# Experiment_4_0_0_0.net
KiCad netlist of a schematic drawn in Altium Designer
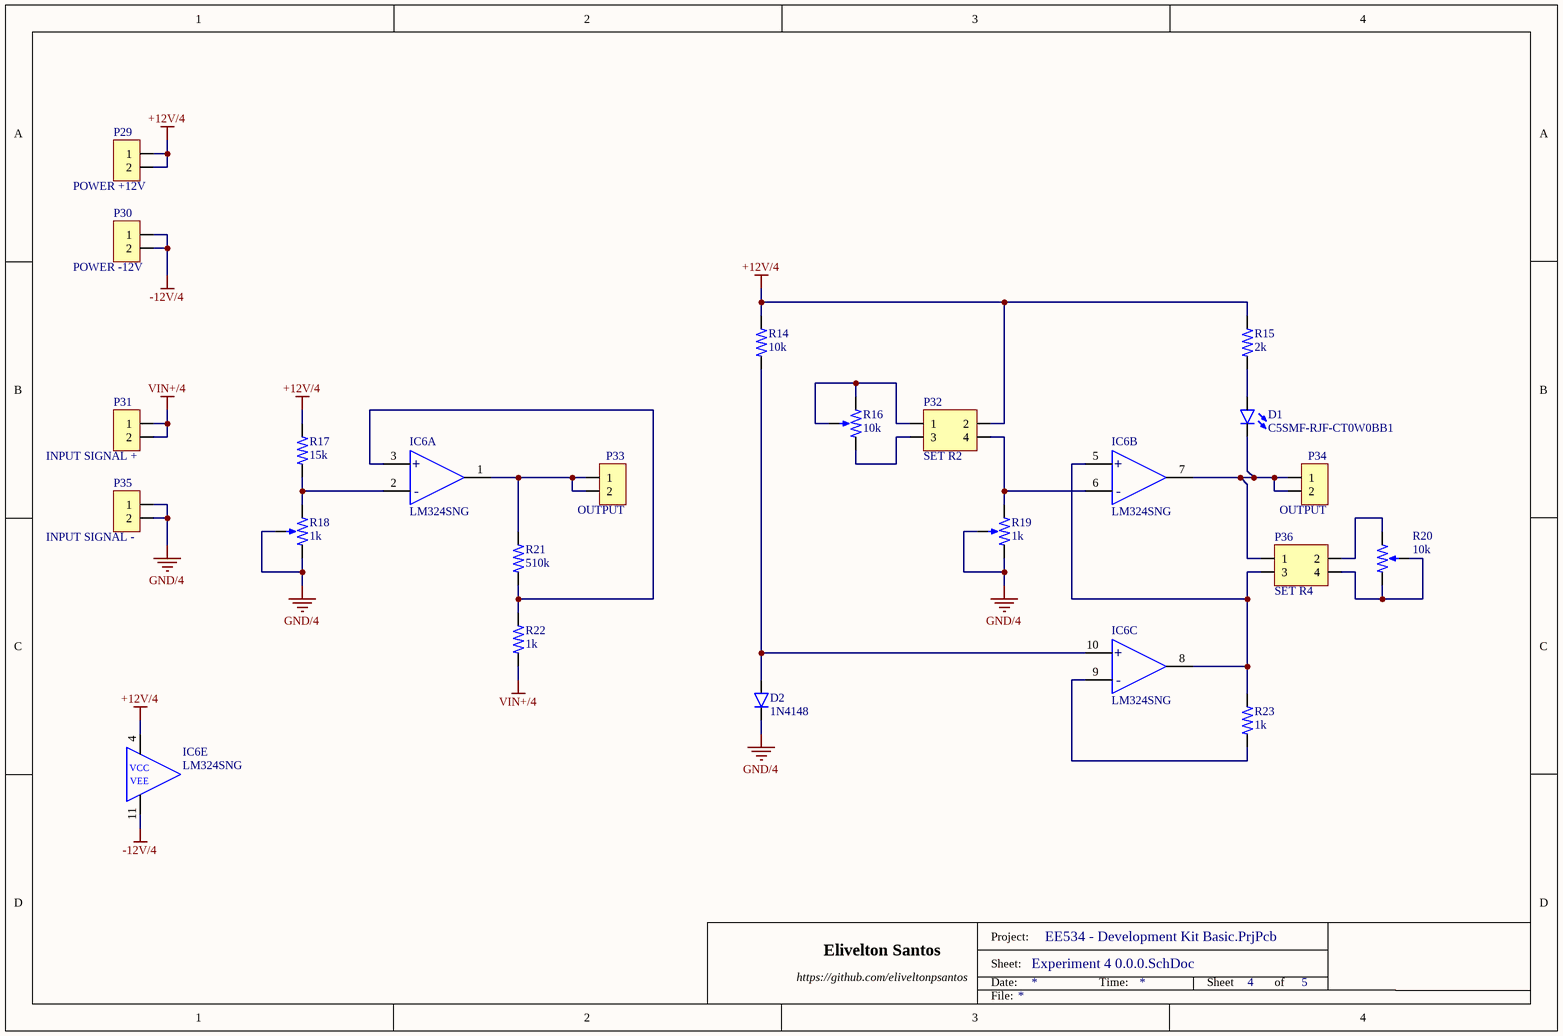
[diagram p0: Experiment 4 0.0.0.SchDoc]

(export (version "E")
  (design (tool "Eeschema 10.0.6"))
  (components
    (comp (ref "D1")
      (value "C5SMF-RJF-CT0W0BB1")
      (footprint "LED-5MM")
      (description "LED RED CLEAR 5MM OVAL T/H")
      (fields (field (name "MANUFACTURER") "Cree Inc."))
      (libsource (lib "Optoelectronics") (part "C5SMF-RJF-CT0W0BB1"))
    )
    (comp (ref "D2")
      (value "1N4148")
      (footprint "DO35-10")
      (description "DIODE GEN PURP 100V 200MA DO35")
      (fields (field (name "MANUFACTURER") "Fairchild Semiconductor"))
      (libsource (lib "Diodes") (part "1N4148"))
    )
    (comp (ref "IC6")
      (value "LM324SNG")
      (footprint "DIP-14")
      (description "IC OP AMP 4CH 14DIP")
      (fields (field (name "MANUFACTURER") "ON Semiconductor"))
      (libsource (lib "ICs") (part "LM324SNG"))
    )
    (comp (ref "P29")
      (value "POWER +12V")
      (footprint "PINHD-1X02 ONCE")
      (description "CONN HEADER 2POS .100\" STR TIN")
      (fields
        (field (name "MANUFACTURER") "Molex, LLC")
        (field (name "MANUFACTURER PART NUMBER") "0901200122")
      )
      (libsource (lib "Connectors") (part "PIN HEADER 1X02 ONCE"))
    )
    (comp (ref "P30")
      (value "POWER -12V")
      (footprint "PINHD-1X02 ONCE")
      (description "CONN HEADER 2POS .100\" STR TIN")
      (fields
        (field (name "MANUFACTURER") "Molex, LLC")
        (field (name "MANUFACTURER PART NUMBER") "0901200122")
      )
      (libsource (lib "Connectors") (part "PIN HEADER 1X02 ONCE"))
    )
    (comp (ref "P31")
      (value "INPUT SIGNAL +")
      (footprint "PINHD-1X02 ONCE")
      (description "CONN HEADER 2POS .100\" STR TIN")
      (fields
        (field (name "MANUFACTURER") "Molex, LLC")
        (field (name "MANUFACTURER PART NUMBER") "0901200122")
      )
      (libsource (lib "Connectors") (part "PIN HEADER 1X02 ONCE"))
    )
    (comp (ref "P32")
      (value "SET R2")
      (footprint "PINHD-2X02")
      (description "CONN HEADER 4POS .100\" STR TIN")
      (fields
        (field (name "MANUFACTURER") "Molex, LLC")
        (field (name "MANUFACTURER PART NUMBER") "0901310122")
      )
      (libsource (lib "Connectors") (part "PIN HEADER 2X02"))
    )
    (comp (ref "P33")
      (value "OUTPUT")
      (footprint "PINHD-1X02 ONCE")
      (description "CONN HEADER 2POS .100\" STR TIN")
      (fields
        (field (name "MANUFACTURER") "Molex, LLC")
        (field (name "MANUFACTURER PART NUMBER") "0901200122")
      )
      (libsource (lib "") (part "PIN HEADER 1X02 ONCE_1"))
    )
    (comp (ref "P34")
      (value "OUTPUT")
      (footprint "PINHD-1X02 ONCE")
      (description "CONN HEADER 2POS .100\" STR TIN")
      (fields
        (field (name "MANUFACTURER") "Molex, LLC")
        (field (name "MANUFACTURER PART NUMBER") "0901200122")
      )
      (libsource (lib "") (part "PIN HEADER 1X02 ONCE_1"))
    )
    (comp (ref "P35")
      (value "INPUT SIGNAL -")
      (footprint "PINHD-1X02 ONCE")
      (description "CONN HEADER 2POS .100\" STR TIN")
      (fields
        (field (name "MANUFACTURER") "Molex, LLC")
        (field (name "MANUFACTURER PART NUMBER") "0901200122")
      )
      (libsource (lib "Connectors") (part "PIN HEADER 1X02 ONCE"))
    )
    (comp (ref "P36")
      (value "SET R4")
      (footprint "PINHD-2X02")
      (description "CONN HEADER 4POS .100\" STR TIN")
      (fields
        (field (name "MANUFACTURER") "Molex, LLC")
        (field (name "MANUFACTURER PART NUMBER") "0901310122")
      )
      (libsource (lib "Connectors") (part "PIN HEADER 2X02"))
    )
    (comp (ref "R14")
      (value "10k")
      (footprint "R Axial 0.25")
      (description "RES 10K OHM 1/4W 5% AXIAL")
      (fields
        (field (name "MANUFACTURER") "Yageo")
        (field (name "MANUFACTURER PART NUMBER") "CFR-25JB-52-10K")
      )
      (libsource (lib "Resistors") (part "CFR-25JB-52-10K"))
    )
    (comp (ref "R15")
      (value "2k")
      (footprint "R Axial 0.25")
      (description "RES 2K OHM 1/4W 5% AXIAL")
      (fields
        (field (name "MANUFACTURER") "Yageo")
        (field (name "MANUFACTURER PART NUMBER") "CFR-25JB-52-2K")
      )
      (libsource (lib "Resistors") (part "CFR-25JB-52-2K"))
    )
    (comp (ref "R16")
      (value "10k")
      (footprint "PV36W")
      (description "TRIMMER 10K OHM 0.5W TH")
      (fields
        (field (name "MANUFACTURER") "Bourns Inc.")
        (field (name "MANUFACTURER PART NUMBER") "PV36W103C01B00")
      )
      (libsource (lib "Resistors") (part "PV36W103C01B00"))
    )
    (comp (ref "R17")
      (value "15k")
      (footprint "R Axial 0.25")
      (description "RES 15K OHM 1/4W 5% AXIAL")
      (fields
        (field (name "MANUFACTURER") "Yageo")
        (field (name "MANUFACTURER PART NUMBER") "CFR-25JB-52-15K")
      )
      (libsource (lib "Resistors") (part "CFR-25JB-52-15K"))
    )
    (comp (ref "R18")
      (value "1k")
      (footprint "PV36W")
      (description "TRIMMER 1K OHM 0.5W TH")
      (fields
        (field (name "MANUFACTURER") "Bourns Inc.")
        (field (name "MANUFACTURER PART NUMBER") "PV36W102C01B00")
      )
      (libsource (lib "Resistors") (part "PV36W102C01B00"))
    )
    (comp (ref "R19")
      (value "1k")
      (footprint "PV36W")
      (description "TRIMMER 1K OHM 0.5W TH")
      (fields
        (field (name "MANUFACTURER") "Bourns Inc.")
        (field (name "MANUFACTURER PART NUMBER") "PV36W102C01B00")
      )
      (libsource (lib "Resistors") (part "PV36W102C01B00"))
    )
    (comp (ref "R20")
      (value "10k")
      (footprint "PV36W")
      (description "TRIMMER 10K OHM 0.5W TH")
      (fields
        (field (name "MANUFACTURER") "Bourns Inc.")
        (field (name "MANUFACTURER PART NUMBER") "PV36W103C01B00")
      )
      (libsource (lib "Resistors") (part "PV36W103C01B00"))
    )
    (comp (ref "R21")
      (value "510k")
      (footprint "R Axial 0.25")
      (description "RES 510K OHM 1/4W 5% AXIAL")
      (fields
        (field (name "MANUFACTURER") "Yageo")
        (field (name "MANUFACTURER PART NUMBER") "CFR-25JB-52-510K")
      )
      (libsource (lib "Resistors") (part "CFR-25JB-52-510K"))
    )
    (comp (ref "R22")
      (value "1k")
      (footprint "R Axial 0.25")
      (description "RES 1K OHM 1/4W 5% AXIAL")
      (fields
        (field (name "MANUFACTURER") "Yageo")
        (field (name "MANUFACTURER PART NUMBER") "CFR-25JB-52-1K")
      )
      (libsource (lib "Resistors") (part "CFR-25JB-52-1K"))
    )
    (comp (ref "R23")
      (value "1k")
      (footprint "R Axial 0.25")
      (description "RES 1K OHM 1/4W 5% AXIAL")
      (fields
        (field (name "MANUFACTURER") "Yageo")
        (field (name "MANUFACTURER PART NUMBER") "CFR-25JB-52-1K")
      )
      (libsource (lib "Resistors") (part "CFR-25JB-52-1K"))
    )
  )
  (nets
    (net (code "1") (name "+12V{slash}4") (class "Default")
      (node (ref "IC6") (pin "4") (pinfunction "VCC_4") (pintype "passive"))
      (node (ref "P29") (pin "1") (pinfunction "1_1") (pintype "passive"))
      (node (ref "P29") (pin "2") (pinfunction "2_2") (pintype "passive"))
      (node (ref "P32") (pin "2") (pinfunction "2_2") (pintype "passive"))
      (node (ref "R14") (pin "2") (pinfunction "2_2") (pintype "passive"))
      (node (ref "R15") (pin "2") (pinfunction "2_2") (pintype "passive"))
      (node (ref "R17") (pin "2") (pinfunction "2_2") (pintype "passive"))
    )
    (net (code "2") (name "-12V{slash}4") (class "Default")
      (node (ref "IC6") (pin "11") (pinfunction "VEE_11") (pintype "passive"))
      (node (ref "P30") (pin "1") (pinfunction "1_1") (pintype "passive"))
      (node (ref "P30") (pin "2") (pinfunction "2_2") (pintype "passive"))
    )
    (net (code "3") (name "GND{slash}4") (class "Default")
      (node (ref "D2") (pin "C") (pinfunction "Cathode_C") (pintype "passive"))
      (node (ref "P35") (pin "1") (pinfunction "1_1") (pintype "passive"))
      (node (ref "P35") (pin "2") (pinfunction "2_2") (pintype "passive"))
      (node (ref "R18") (pin "2") (pinfunction "2_2") (pintype "passive"))
      (node (ref "R18") (pin "3") (pinfunction "3_3") (pintype "passive"))
      (node (ref "R19") (pin "2") (pinfunction "2_2") (pintype "passive"))
      (node (ref "R19") (pin "3") (pinfunction "3_3") (pintype "passive"))
    )
    (net (code "4") (name "Net-(D1-Anode)") (class "Default")
      (node (ref "D1") (pin "1") (pinfunction "Anode_1") (pintype "passive"))
      (node (ref "R15") (pin "1") (pinfunction "1_1") (pintype "passive"))
    )
    (net (code "5") (name "Net-(D1-Cathode)") (class "Default")
      (node (ref "D1") (pin "2") (pinfunction "Cathode_2") (pintype "passive"))
      (node (ref "IC6") (pin "7") (pinfunction "OUTPUT_2_7") (pintype "passive"))
      (node (ref "P34") (pin "1") (pinfunction "1_1") (pintype "passive"))
      (node (ref "P34") (pin "2") (pinfunction "2_2") (pintype "passive"))
      (node (ref "P36") (pin "1") (pinfunction "1_1") (pintype "passive"))
    )
    (net (code "6") (name "Net-(D2-Anode)") (class "Default")
      (node (ref "D2") (pin "A") (pinfunction "Anode_A") (pintype "passive"))
      (node (ref "IC6") (pin "10") (pinfunction "INPUT_+_3_10") (pintype "passive"))
      (node (ref "R14") (pin "1") (pinfunction "1_1") (pintype "passive"))
    )
    (net (code "7") (name "Net-(IC6A-INPUT_+_1)") (class "Default")
      (node (ref "IC6") (pin "3") (pinfunction "INPUT_+_1_3") (pintype "passive"))
      (node (ref "R21") (pin "1") (pinfunction "1_1") (pintype "passive"))
      (node (ref "R22") (pin "2") (pinfunction "2_2") (pintype "passive"))
    )
    (net (code "8") (name "Net-(IC6A-INPUT_-_1)") (class "Default")
      (node (ref "IC6") (pin "2") (pinfunction "INPUT_-_1_2") (pintype "passive"))
      (node (ref "R17") (pin "1") (pinfunction "1_1") (pintype "passive"))
      (node (ref "R18") (pin "1") (pinfunction "1_1") (pintype "passive"))
    )
    (net (code "9") (name "Net-(IC6A-OUTPUT_1)") (class "Default")
      (node (ref "IC6") (pin "1") (pinfunction "OUTPUT_1_1") (pintype "passive"))
      (node (ref "P33") (pin "1") (pinfunction "1_1") (pintype "passive"))
      (node (ref "P33") (pin "2") (pinfunction "2_2") (pintype "passive"))
      (node (ref "R21") (pin "2") (pinfunction "2_2") (pintype "passive"))
    )
    (net (code "10") (name "Net-(IC6B-INPUT_+_2)") (class "Default")
      (node (ref "IC6") (pin "5") (pinfunction "INPUT_+_2_5") (pintype "passive"))
      (node (ref "IC6") (pin "8") (pinfunction "OUTPUT_3_8") (pintype "passive"))
      (node (ref "P36") (pin "3") (pinfunction "3_3") (pintype "passive"))
      (node (ref "R23") (pin "2") (pinfunction "2_2") (pintype "passive"))
    )
    (net (code "11") (name "Net-(IC6B-INPUT_-_2)") (class "Default")
      (node (ref "IC6") (pin "6") (pinfunction "INPUT_-_2_6") (pintype "passive"))
      (node (ref "P32") (pin "4") (pinfunction "4_4") (pintype "passive"))
      (node (ref "R19") (pin "1") (pinfunction "1_1") (pintype "passive"))
    )
    (net (code "12") (name "Net-(IC6C-INPUT_-_3)") (class "Default")
      (node (ref "IC6") (pin "9") (pinfunction "INPUT_-_3_9") (pintype "passive"))
      (node (ref "R23") (pin "1") (pinfunction "1_1") (pintype "passive"))
    )
    (net (code "13") (name "Net-(P32-Pad1)") (class "Default")
      (node (ref "P32") (pin "1") (pinfunction "1_1") (pintype "passive"))
      (node (ref "R16") (pin "1") (pinfunction "1_1") (pintype "passive"))
      (node (ref "R16") (pin "2") (pinfunction "2_2") (pintype "passive"))
    )
    (net (code "14") (name "Net-(P32-Pad3)") (class "Default")
      (node (ref "P32") (pin "3") (pinfunction "3_3") (pintype "passive"))
      (node (ref "R16") (pin "3") (pinfunction "3_3") (pintype "passive"))
    )
    (net (code "15") (name "Net-(P36-Pad2)") (class "Default")
      (node (ref "P36") (pin "2") (pinfunction "2_2") (pintype "passive"))
      (node (ref "R20") (pin "3") (pinfunction "3_3") (pintype "passive"))
    )
    (net (code "16") (name "Net-(P36-Pad4)") (class "Default")
      (node (ref "P36") (pin "4") (pinfunction "4_4") (pintype "passive"))
      (node (ref "R20") (pin "1") (pinfunction "1_1") (pintype "passive"))
      (node (ref "R20") (pin "2") (pinfunction "2_2") (pintype "passive"))
    )
    (net (code "17") (name "VIN+{slash}4") (class "Default")
      (node (ref "P31") (pin "1") (pinfunction "1_1") (pintype "passive"))
      (node (ref "P31") (pin "2") (pinfunction "2_2") (pintype "passive"))
      (node (ref "R22") (pin "1") (pinfunction "1_1") (pintype "passive"))
    )
  )
)
